# Motor_and_Encoder.net
KiCad netlist of a schematic drawn in Altium Designer
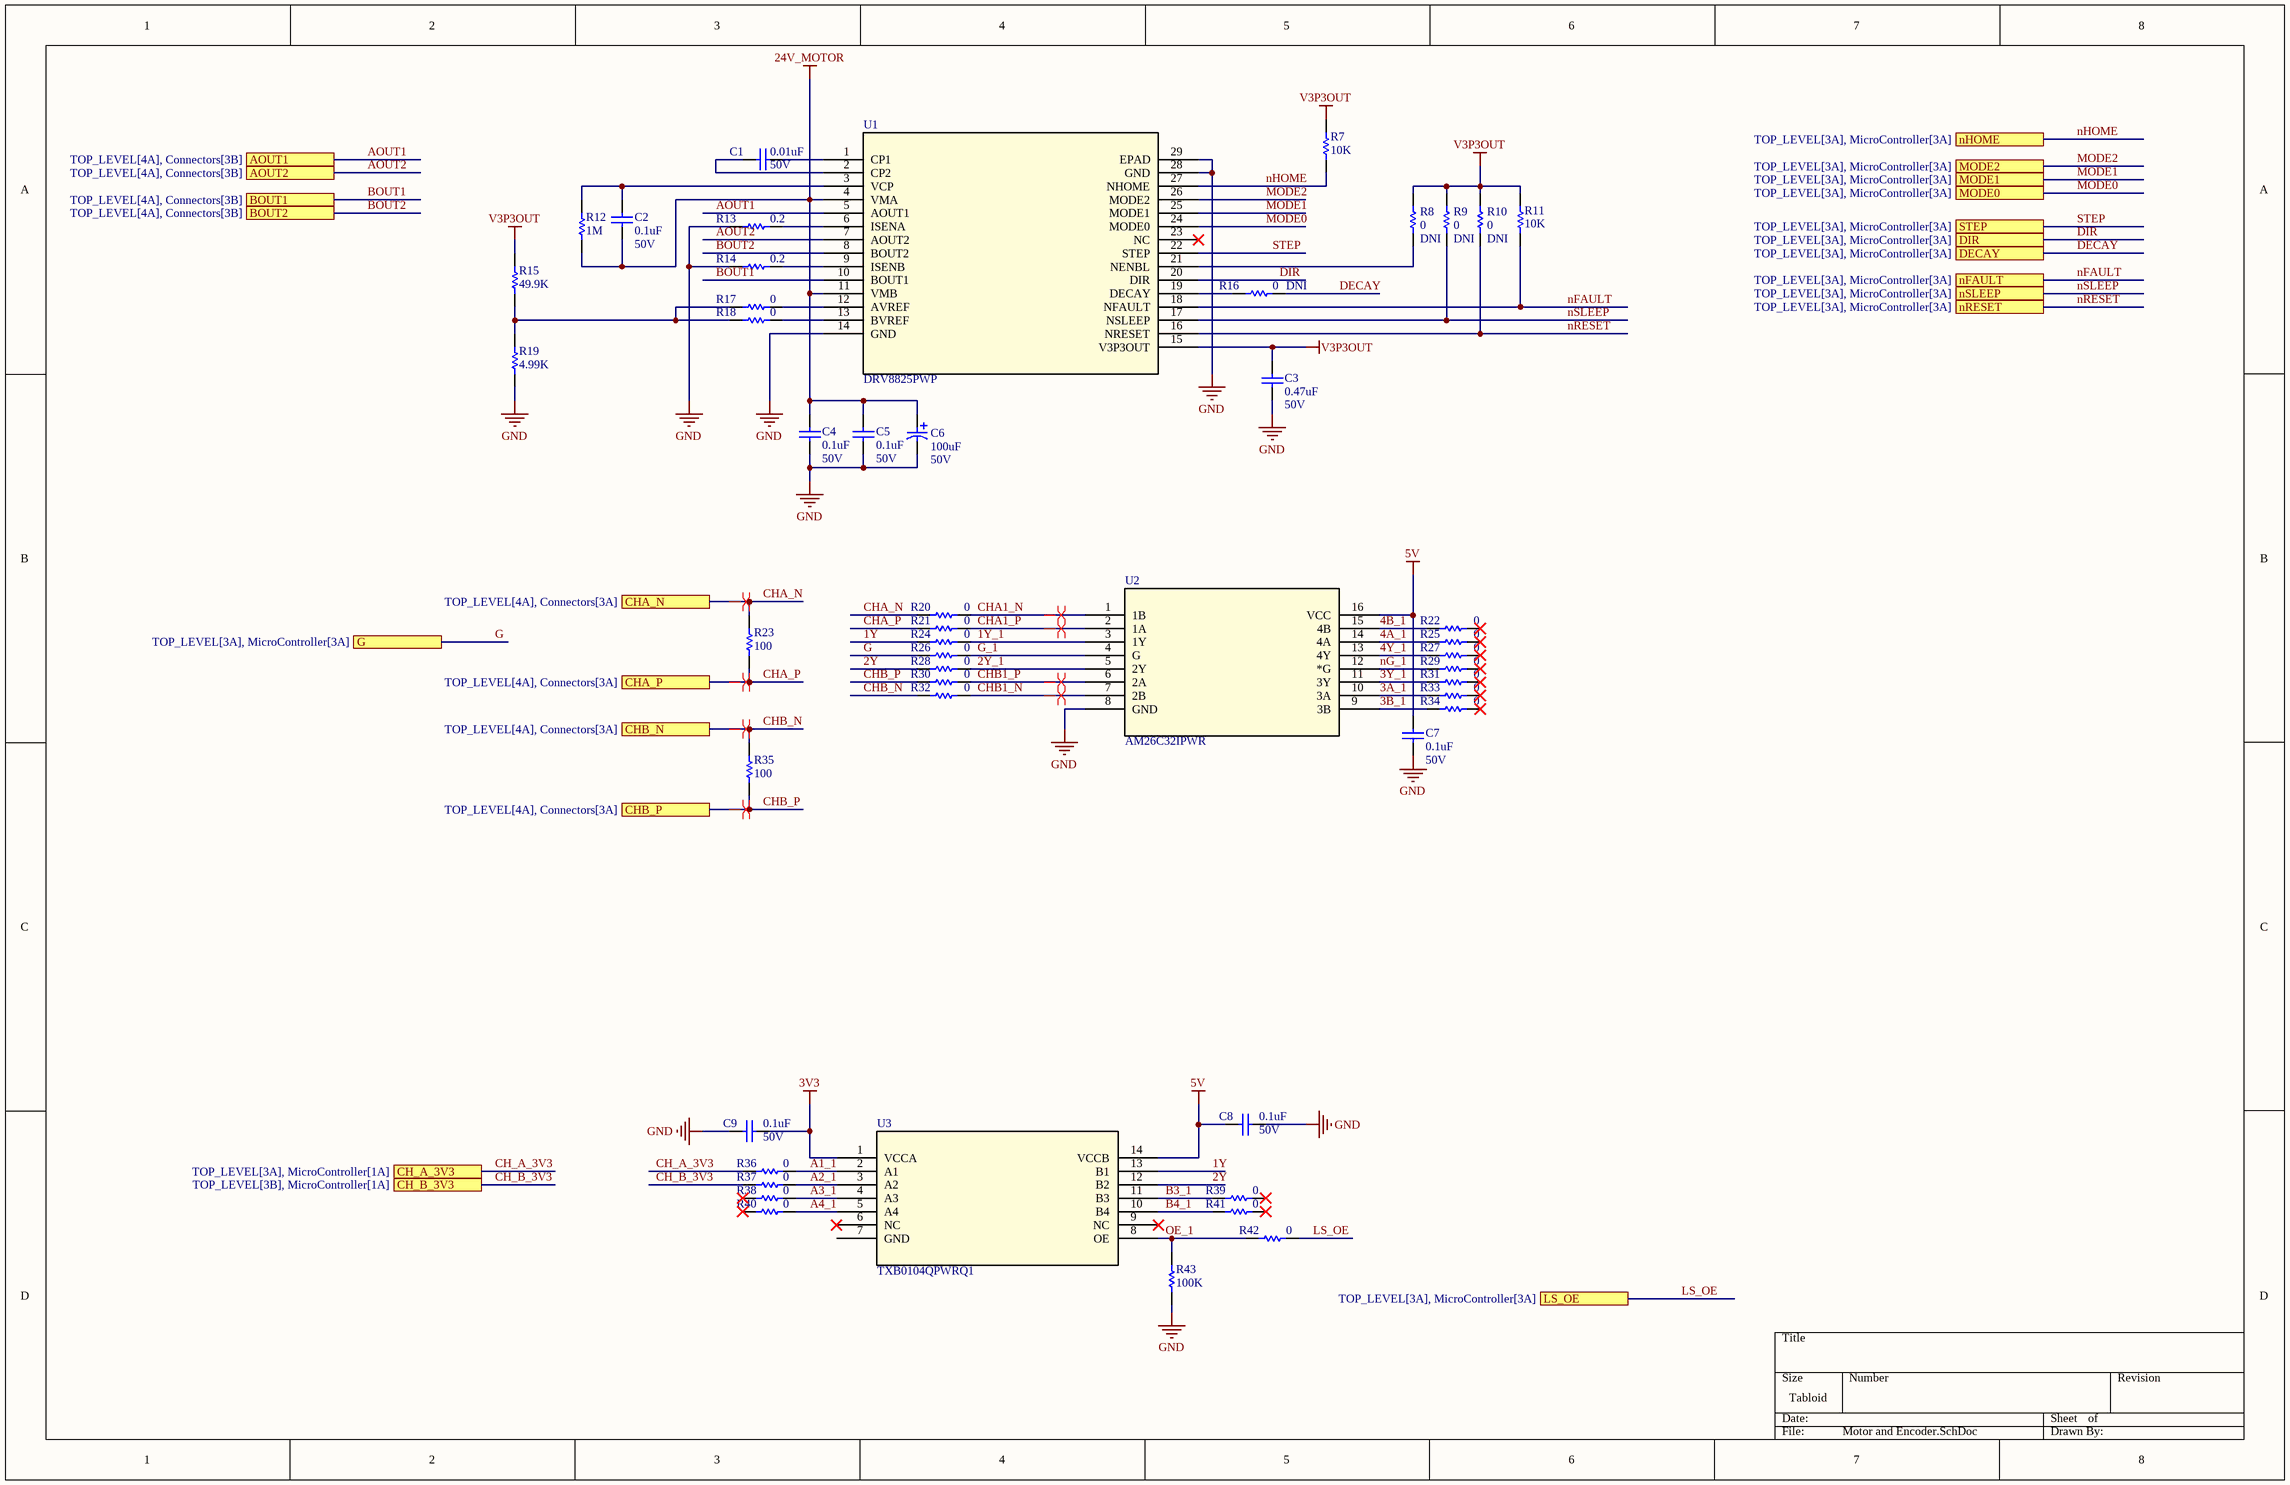
[diagram p0: Motor and Encoder.SchDoc]

(export (version "E")
  (design (tool "Eeschema 10.0.6"))
  (components
    (comp (ref "C1")
      (value "0.01uF")
      (footprint "DEFAULT_CAPACITOR_0805")
      (description "CAP CER 10000PF 50V X7R 0805")
      (fields
        (field (name "MANUFACTURER") "Cal-Chip Electronics, Inc.")
        (field (name "RATING") "50V")
        (field (name "Comment") "KGM21NR71H103KT")
      )
      (libsource (lib "Avery Altium Llibrary") (part "KGM21NR71H103KT"))
    )
    (comp (ref "C2")
      (value "0.1uF")
      (footprint "DEFAULT_CAPACITOR_0805")
      (description "CAP CER 0.1UF 50V X7R 0805")
      (fields
        (field (name "MANUFACTURER") "Cal-Chip Electronics, Inc.")
        (field (name "RATING") "50V")
        (field (name "Comment") "KGM21NR71H104KT")
      )
      (libsource (lib "Avery Altium Llibrary") (part "KGM21NR71H104KT"))
    )
    (comp (ref "C3")
      (value "0.47uF")
      (footprint "DEFAULT_CAPACITOR_0805")
      (description "CAP CER 0.47UF 50V X7R 0805")
      (fields
        (field (name "MANUFACTURER") "Cal-Chip Electronics, Inc.")
        (field (name "RATING") "50V")
        (field (name "Comment") "GRM21BR71H474KA88L")
      )
      (libsource (lib "Avery Altium Llibrary") (part "GRM21BR71H474KA88L"))
    )
    (comp (ref "C4")
      (value "0.1uF")
      (footprint "DEFAULT_CAPACITOR_0805")
      (description "CAP CER 0.1UF 50V X7R 0805")
      (fields
        (field (name "MANUFACTURER") "Cal-Chip Electronics, Inc.")
        (field (name "RATING") "50V")
        (field (name "Comment") "KGM21NR71H104KT")
      )
      (libsource (lib "Avery Altium Llibrary") (part "KGM21NR71H104KT"))
    )
    (comp (ref "C5")
      (value "0.1uF")
      (footprint "DEFAULT_CAPACITOR_0805")
      (description "CAP CER 0.1UF 50V X7R 0805")
      (fields
        (field (name "MANUFACTURER") "Cal-Chip Electronics, Inc.")
        (field (name "RATING") "50V")
        (field (name "Comment") "KGM21NR71H104KT")
      )
      (libsource (lib "Avery Altium Llibrary") (part "KGM21NR71H104KT"))
    )
    (comp (ref "C6")
      (value "100uF")
      (footprint "UWT1H101MNL1GS")
      (description "CAP ALUM 100UF 20% 50V SMD")
      (fields
        (field (name "MANUFACTURER_PART_NUMBER") "UWT1H101MNL1GS")
        (field (name "RATING") "50V")
        (field (name "COPYRIGHT") "Copyright (C) 2026 Ultra Librarian. All rights reserved.")
      )
      (libsource (lib "Avery Schem Library") (part "UWT1H101MNL1GS"))
    )
    (comp (ref "C7")
      (value "0.1uF")
      (footprint "DEFAULT_CAPACITOR_0805")
      (description "CAP CER 0.1UF 50V X7R 0805")
      (fields
        (field (name "MANUFACTURER") "Cal-Chip Electronics, Inc.")
        (field (name "RATING") "50V")
        (field (name "Comment") "KGM21NR71H104KT")
      )
      (libsource (lib "Avery Altium Llibrary") (part "KGM21NR71H104KT"))
    )
    (comp (ref "C8")
      (value "0.1uF")
      (footprint "DEFAULT_CAPACITOR_0805")
      (description "CAP CER 0.1UF 50V X7R 0805")
      (fields
        (field (name "MANUFACTURER") "Cal-Chip Electronics, Inc.")
        (field (name "RATING") "50V")
        (field (name "Comment") "KGM21NR71H104KT")
      )
      (libsource (lib "Avery Altium Llibrary") (part "KGM21NR71H104KT"))
    )
    (comp (ref "C9")
      (value "0.1uF")
      (footprint "DEFAULT_CAPACITOR_0805")
      (description "CAP CER 0.1UF 50V X7R 0805")
      (fields
        (field (name "MANUFACTURER") "Cal-Chip Electronics, Inc.")
        (field (name "RATING") "50V")
        (field (name "Comment") "KGM21NR71H104KT")
      )
      (libsource (lib "Avery Altium Llibrary") (part "KGM21NR71H104KT"))
    )
    (comp (ref "R7")
      (value "10K")
      (footprint "DEFAULT_RESISTOR_0805")
      (description "RES SMD 10K OHM 1% 1/4W 0805")
      (fields (field (name "POWER") "1/4W") (field (name "TOLERANCE") "1%"))
      (libsource (lib "Avery Altium Llibrary") (part "CRCW080510K0FKEA"))
    )
    (comp (ref "R8")
      (value "DNI")
      (footprint "DEFAULT_RESISTOR_0805")
      (description "RES 0 OHM JUMPER 1/8W 0805")
      (fields (field (name "POWER") "1/8W") (field (name "ALTIUM_VALUE") "0"))
      (libsource (lib "Avery Altium Llibrary") (part "RC0805JR-070RL"))
    )
    (comp (ref "R9")
      (value "DNI")
      (footprint "DEFAULT_RESISTOR_0805")
      (description "RES 0 OHM JUMPER 1/8W 0805")
      (fields (field (name "POWER") "1/8W") (field (name "ALTIUM_VALUE") "0"))
      (libsource (lib "Avery Altium Llibrary") (part "RC0805JR-070RL"))
    )
    (comp (ref "R10")
      (value "DNI")
      (footprint "DEFAULT_RESISTOR_0805")
      (description "RES 0 OHM JUMPER 1/8W 0805")
      (fields (field (name "POWER") "1/8W") (field (name "ALTIUM_VALUE") "0"))
      (libsource (lib "Avery Altium Llibrary") (part "RC0805JR-070RL"))
    )
    (comp (ref "R11")
      (value "10K")
      (footprint "DEFAULT_RESISTOR_0805")
      (description "RES SMD 10K OHM 1% 1/4W 0805")
      (fields (field (name "POWER") "1/4W") (field (name "TOLERANCE") "1%"))
      (libsource (lib "Avery Altium Llibrary") (part "CRCW080510K0FKEA"))
    )
    (comp (ref "R12")
      (value "1M")
      (footprint "DEFAULT_RESISTOR_0805")
      (description "RES SMD 1M OHM 1% 1/4W 0805")
      (fields (field (name "POWER") "1/4W") (field (name "TOLERANCE") "1%"))
      (libsource (lib "Avery Altium Llibrary") (part "CRCW08051M00FKEA"))
    )
    (comp (ref "R13")
      (value "0.2")
      (footprint "DEFAULT_RESISTOR_0805")
      (description "RES 0.2 OHM 1% 1/2W 0805")
      (fields (field (name "TOLERANCE") "1%") (field (name "Comment") "ERJ-6DSFR20V"))
      (libsource (lib "Avery Altium Llibrary") (part "ERJ-6DSFR20V"))
    )
    (comp (ref "R14")
      (value "0.2")
      (footprint "DEFAULT_RESISTOR_0805")
      (description "RES 0.2 OHM 1% 1/2W 0805")
      (fields (field (name "TOLERANCE") "1%") (field (name "Comment") "ERJ-6DSFR20V"))
      (libsource (lib "Avery Altium Llibrary") (part "ERJ-6DSFR20V"))
    )
    (comp (ref "R15")
      (value "49.9K")
      (footprint "DEFAULT_RESISTOR_0805")
      (description "RES 49.9K OHM 1% 1/8W 0805")
      (fields (field (name "POWER") "1/8W") (field (name "TOLERANCE") "1%"))
      (libsource (lib "Avery Altium Llibrary") (part "RMCF0805FT49K9"))
    )
    (comp (ref "R16")
      (value "DNI")
      (footprint "DEFAULT_RESISTOR_0805")
      (description "RES 0 OHM JUMPER 1/8W 0805")
      (fields (field (name "POWER") "1/8W") (field (name "ALTIUM_VALUE") "0"))
      (libsource (lib "Avery Altium Llibrary") (part "RC0805JR-070RL"))
    )
    (comp (ref "R17")
      (value "0")
      (footprint "DEFAULT_RESISTOR_0805")
      (description "RES 0 OHM JUMPER 1/8W 0805")
      (fields (field (name "POWER") "1/8W") (field (name "Comment") "RC0805JR-070RL"))
      (libsource (lib "Avery Altium Llibrary") (part "RC0805JR-070RL"))
    )
    (comp (ref "R18")
      (value "0")
      (footprint "DEFAULT_RESISTOR_0805")
      (description "RES 0 OHM JUMPER 1/8W 0805")
      (fields (field (name "POWER") "1/8W") (field (name "Comment") "RC0805JR-070RL"))
      (libsource (lib "Avery Altium Llibrary") (part "RC0805JR-070RL"))
    )
    (comp (ref "R19")
      (value "4.99K")
      (footprint "DEFAULT_RESISTOR_0805")
      (description "RES 4.99K OHM 1% 1/8W 0805")
      (fields (field (name "POWER") "1/8W") (field (name "TOLERANCE") "1%"))
      (libsource (lib "Avery Altium Llibrary") (part "RMCF0805FT4K99"))
    )
    (comp (ref "R20")
      (value "0")
      (footprint "DEFAULT_RESISTOR_0805")
      (description "RES 0 OHM JUMPER 1/8W 0805")
      (fields (field (name "POWER") "1/8W") (field (name "Comment") "RC0805JR-070RL"))
      (libsource (lib "Avery Altium Llibrary") (part "RC0805JR-070RL"))
    )
    (comp (ref "R21")
      (value "0")
      (footprint "DEFAULT_RESISTOR_0805")
      (description "RES 0 OHM JUMPER 1/8W 0805")
      (fields (field (name "POWER") "1/8W") (field (name "Comment") "RC0805JR-070RL"))
      (libsource (lib "Avery Altium Llibrary") (part "RC0805JR-070RL"))
    )
    (comp (ref "R22")
      (value "0")
      (footprint "DEFAULT_RESISTOR_0805")
      (description "RES 0 OHM JUMPER 1/8W 0805")
      (fields (field (name "POWER") "1/8W") (field (name "Comment") "RC0805JR-070RL"))
      (libsource (lib "Avery Altium Llibrary") (part "RC0805JR-070RL"))
    )
    (comp (ref "R23")
      (value "100")
      (footprint "DEFAULT_RESISTOR_0805")
      (description "RES SMD 100 OHM 1% 1/4W 0805")
      (fields (field (name "POWER") "1/4W") (field (name "TOLERANCE") "1%"))
      (libsource (lib "Avery Altium Llibrary") (part "CRCW0805100RFKEA"))
    )
    (comp (ref "R24")
      (value "0")
      (footprint "DEFAULT_RESISTOR_0805")
      (description "RES 0 OHM JUMPER 1/8W 0805")
      (fields (field (name "POWER") "1/8W") (field (name "Comment") "RC0805JR-070RL"))
      (libsource (lib "Avery Altium Llibrary") (part "RC0805JR-070RL"))
    )
    (comp (ref "R25")
      (value "0")
      (footprint "DEFAULT_RESISTOR_0805")
      (description "RES 0 OHM JUMPER 1/8W 0805")
      (fields (field (name "POWER") "1/8W") (field (name "Comment") "RC0805JR-070RL"))
      (libsource (lib "Avery Altium Llibrary") (part "RC0805JR-070RL"))
    )
    (comp (ref "R26")
      (value "0")
      (footprint "DEFAULT_RESISTOR_0805")
      (description "RES 0 OHM JUMPER 1/8W 0805")
      (fields (field (name "POWER") "1/8W") (field (name "Comment") "RC0805JR-070RL"))
      (libsource (lib "Avery Altium Llibrary") (part "RC0805JR-070RL"))
    )
    (comp (ref "R27")
      (value "0")
      (footprint "DEFAULT_RESISTOR_0805")
      (description "RES 0 OHM JUMPER 1/8W 0805")
      (fields (field (name "POWER") "1/8W") (field (name "Comment") "RC0805JR-070RL"))
      (libsource (lib "Avery Altium Llibrary") (part "RC0805JR-070RL"))
    )
    (comp (ref "R28")
      (value "0")
      (footprint "DEFAULT_RESISTOR_0805")
      (description "RES 0 OHM JUMPER 1/8W 0805")
      (fields (field (name "POWER") "1/8W") (field (name "Comment") "RC0805JR-070RL"))
      (libsource (lib "Avery Altium Llibrary") (part "RC0805JR-070RL"))
    )
    (comp (ref "R29")
      (value "0")
      (footprint "DEFAULT_RESISTOR_0805")
      (description "RES 0 OHM JUMPER 1/8W 0805")
      (fields (field (name "POWER") "1/8W") (field (name "Comment") "RC0805JR-070RL"))
      (libsource (lib "Avery Altium Llibrary") (part "RC0805JR-070RL"))
    )
    (comp (ref "R30")
      (value "0")
      (footprint "DEFAULT_RESISTOR_0805")
      (description "RES 0 OHM JUMPER 1/8W 0805")
      (fields (field (name "POWER") "1/8W") (field (name "Comment") "RC0805JR-070RL"))
      (libsource (lib "Avery Altium Llibrary") (part "RC0805JR-070RL"))
    )
    (comp (ref "R31")
      (value "0")
      (footprint "DEFAULT_RESISTOR_0805")
      (description "RES 0 OHM JUMPER 1/8W 0805")
      (fields (field (name "POWER") "1/8W") (field (name "Comment") "RC0805JR-070RL"))
      (libsource (lib "Avery Altium Llibrary") (part "RC0805JR-070RL"))
    )
    (comp (ref "R32")
      (value "0")
      (footprint "DEFAULT_RESISTOR_0805")
      (description "RES 0 OHM JUMPER 1/8W 0805")
      (fields (field (name "POWER") "1/8W") (field (name "Comment") "RC0805JR-070RL"))
      (libsource (lib "Avery Altium Llibrary") (part "RC0805JR-070RL"))
    )
    (comp (ref "R33")
      (value "0")
      (footprint "DEFAULT_RESISTOR_0805")
      (description "RES 0 OHM JUMPER 1/8W 0805")
      (fields (field (name "POWER") "1/8W") (field (name "Comment") "RC0805JR-070RL"))
      (libsource (lib "Avery Altium Llibrary") (part "RC0805JR-070RL"))
    )
    (comp (ref "R34")
      (value "0")
      (footprint "DEFAULT_RESISTOR_0805")
      (description "RES 0 OHM JUMPER 1/8W 0805")
      (fields (field (name "POWER") "1/8W") (field (name "Comment") "RC0805JR-070RL"))
      (libsource (lib "Avery Altium Llibrary") (part "RC0805JR-070RL"))
    )
    (comp (ref "R35")
      (value "100")
      (footprint "DEFAULT_RESISTOR_0805")
      (description "RES SMD 100 OHM 1% 1/4W 0805")
      (fields (field (name "POWER") "1/4W") (field (name "TOLERANCE") "1%"))
      (libsource (lib "Avery Altium Llibrary") (part "CRCW0805100RFKEA"))
    )
    (comp (ref "R36")
      (value "0")
      (footprint "DEFAULT_RESISTOR_0805")
      (description "RES 0 OHM JUMPER 1/8W 0805")
      (fields (field (name "POWER") "1/8W") (field (name "Comment") "RC0805JR-070RL"))
      (libsource (lib "Avery Altium Llibrary") (part "RC0805JR-070RL"))
    )
    (comp (ref "R37")
      (value "0")
      (footprint "DEFAULT_RESISTOR_0805")
      (description "RES 0 OHM JUMPER 1/8W 0805")
      (fields (field (name "POWER") "1/8W") (field (name "Comment") "RC0805JR-070RL"))
      (libsource (lib "Avery Altium Llibrary") (part "RC0805JR-070RL"))
    )
    (comp (ref "R38")
      (value "0")
      (footprint "DEFAULT_RESISTOR_0805")
      (description "RES 0 OHM JUMPER 1/8W 0805")
      (fields (field (name "POWER") "1/8W") (field (name "Comment") "RC0805JR-070RL"))
      (libsource (lib "Avery Altium Llibrary") (part "RC0805JR-070RL"))
    )
    (comp (ref "R39")
      (value "0")
      (footprint "DEFAULT_RESISTOR_0805")
      (description "RES 0 OHM JUMPER 1/8W 0805")
      (fields (field (name "POWER") "1/8W") (field (name "Comment") "RC0805JR-070RL"))
      (libsource (lib "Avery Altium Llibrary") (part "RC0805JR-070RL"))
    )
    (comp (ref "R40")
      (value "0")
      (footprint "DEFAULT_RESISTOR_0805")
      (description "RES 0 OHM JUMPER 1/8W 0805")
      (fields (field (name "POWER") "1/8W") (field (name "Comment") "RC0805JR-070RL"))
      (libsource (lib "Avery Altium Llibrary") (part "RC0805JR-070RL"))
    )
    (comp (ref "R41")
      (value "0")
      (footprint "DEFAULT_RESISTOR_0805")
      (description "RES 0 OHM JUMPER 1/8W 0805")
      (fields (field (name "POWER") "1/8W") (field (name "Comment") "RC0805JR-070RL"))
      (libsource (lib "Avery Altium Llibrary") (part "RC0805JR-070RL"))
    )
    (comp (ref "R42")
      (value "0")
      (footprint "DEFAULT_RESISTOR_0805")
      (description "RES 0 OHM JUMPER 1/8W 0805")
      (fields (field (name "POWER") "1/8W") (field (name "Comment") "RC0805JR-070RL"))
      (libsource (lib "Avery Altium Llibrary") (part "RC0805JR-070RL"))
    )
    (comp (ref "R43")
      (value "100K")
      (footprint "DEFAULT_RESISTOR_0805")
      (description "RES 100K OHM 1% 1/8W 0805")
      (fields (field (name "POWER") "1/8W") (field (name "TOLERANCE") "1%"))
      (libsource (lib "Avery Altium Llibrary") (part "RC0805FR-07100KL"))
    )
    (comp (ref "U1")
      (value "DRV8825PWP")
      (footprint "DRV8825PWP - 28HTSSTOP")
      (fields (field (name "COPYRIGHT") "Copyright (C) 2026 Ultra Librarian. All rights reserved."))
      (libsource (lib "Avery Schem Library") (part "DRV8825PWP"))
    )
    (comp (ref "U2")
      (value "AM26C32IPWR")
      (footprint "AM26C32IPWR")
      (description "Quadruple Differential Line Receiver 16-TSSOP -40 to 85")
      (fields (field (name "COPYRIGHT") "Copyright (C) 2025 Ultra Librarian. All rights reserved."))
      (libsource (lib "Avery Schem Library") (part "AM26C32IPWR"))
    )
    (comp (ref "U3")
      (value "TXB0104QPWRQ1")
      (footprint "TXB0104QPWRQ1 - 14TSSOP")
      (fields (field (name "COPYRIGHT") "Copyright (C) 2025 Ultra Librarian. All rights reserved."))
      (libsource (lib "Avery Schem Library") (part "TXB0104QPWRQ1"))
    )
  )
  (nets
    (net (code "1") (name "/1Y") (class "Default")
      (node (ref "R24") (pin "2") (pinfunction "2_2") (pintype "passive"))
      (node (ref "U3") (pin "13") (pinfunction "B1_13") (pintype "passive"))
    )
    (net (code "2") (name "/1Y_1") (class "Default")
      (node (ref "R24") (pin "1") (pinfunction "1_1") (pintype "passive"))
      (node (ref "U2") (pin "3") (pinfunction "1Y_3") (pintype "passive"))
    )
    (net (code "3") (name "/2Y") (class "Default")
      (node (ref "R28") (pin "2") (pinfunction "2_2") (pintype "passive"))
      (node (ref "U3") (pin "12") (pinfunction "B2_12") (pintype "passive"))
    )
    (net (code "4") (name "/2Y_1") (class "Default")
      (node (ref "R28") (pin "1") (pinfunction "1_1") (pintype "passive"))
      (node (ref "U2") (pin "5") (pinfunction "2Y_5") (pintype "passive"))
    )
    (net (code "5") (name "/3A_1") (class "Default")
      (node (ref "R33") (pin "2") (pinfunction "2_2") (pintype "passive"))
      (node (ref "U2") (pin "10") (pinfunction "3A_10") (pintype "passive"))
    )
    (net (code "6") (name "/3B_1") (class "Default")
      (node (ref "R34") (pin "2") (pinfunction "2_2") (pintype "passive"))
      (node (ref "U2") (pin "9") (pinfunction "3B_9") (pintype "passive"))
    )
    (net (code "7") (name "/3Y_1") (class "Default")
      (node (ref "R31") (pin "2") (pinfunction "2_2") (pintype "passive"))
      (node (ref "U2") (pin "11") (pinfunction "3Y_11") (pintype "passive"))
    )
    (net (code "8") (name "/4A_1") (class "Default")
      (node (ref "R25") (pin "2") (pinfunction "2_2") (pintype "passive"))
      (node (ref "U2") (pin "14") (pinfunction "4A_14") (pintype "passive"))
    )
    (net (code "9") (name "/4B_1") (class "Default")
      (node (ref "R22") (pin "2") (pinfunction "2_2") (pintype "passive"))
      (node (ref "U2") (pin "15") (pinfunction "4B_15") (pintype "passive"))
    )
    (net (code "10") (name "/4Y_1") (class "Default")
      (node (ref "R27") (pin "2") (pinfunction "2_2") (pintype "passive"))
      (node (ref "U2") (pin "13") (pinfunction "4Y_13") (pintype "passive"))
    )
    (net (code "11") (name "/A1_1") (class "Default")
      (node (ref "R36") (pin "1") (pinfunction "1_1") (pintype "passive"))
      (node (ref "U3") (pin "2") (pinfunction "A1_2") (pintype "passive"))
    )
    (net (code "12") (name "/A2_1") (class "Default")
      (node (ref "R37") (pin "1") (pinfunction "1_1") (pintype "passive"))
      (node (ref "U3") (pin "3") (pinfunction "A2_3") (pintype "passive"))
    )
    (net (code "13") (name "/A3_1") (class "Default")
      (node (ref "R38") (pin "1") (pinfunction "1_1") (pintype "passive"))
      (node (ref "U3") (pin "4") (pinfunction "A3_4") (pintype "passive"))
    )
    (net (code "14") (name "/A4_1") (class "Default")
      (node (ref "R40") (pin "1") (pinfunction "1_1") (pintype "passive"))
      (node (ref "U3") (pin "5") (pinfunction "A4_5") (pintype "passive"))
    )
    (net (code "15") (name "/AOUT1") (class "Default")
      (node (ref "U1") (pin "5") (pinfunction "AOUT1_5") (pintype "passive"))
    )
    (net (code "16") (name "/AOUT2") (class "Default")
      (node (ref "U1") (pin "7") (pinfunction "AOUT2_7") (pintype "passive"))
    )
    (net (code "17") (name "/B3_1") (class "Default")
      (node (ref "R39") (pin "2") (pinfunction "2_2") (pintype "passive"))
      (node (ref "U3") (pin "11") (pinfunction "B3_11") (pintype "passive"))
    )
    (net (code "18") (name "/B4_1") (class "Default")
      (node (ref "R41") (pin "2") (pinfunction "2_2") (pintype "passive"))
      (node (ref "U3") (pin "10") (pinfunction "B4_10") (pintype "passive"))
    )
    (net (code "19") (name "/BOUT1") (class "Default")
      (node (ref "U1") (pin "10") (pinfunction "BOUT1_10") (pintype "passive"))
    )
    (net (code "20") (name "/BOUT2") (class "Default")
      (node (ref "U1") (pin "8") (pinfunction "BOUT2_8") (pintype "passive"))
    )
    (net (code "21") (name "/CHA1_N") (class "Default")
      (node (ref "R20") (pin "1") (pinfunction "1_1") (pintype "passive"))
      (node (ref "U2") (pin "1") (pinfunction "1B_1") (pintype "passive"))
    )
    (net (code "22") (name "/CHA1_P") (class "Default")
      (node (ref "R21") (pin "1") (pinfunction "1_1") (pintype "passive"))
      (node (ref "U2") (pin "2") (pinfunction "1A_2") (pintype "passive"))
    )
    (net (code "23") (name "/CHA_N") (class "Default")
      (node (ref "R20") (pin "2") (pinfunction "2_2") (pintype "passive"))
      (node (ref "R23") (pin "1") (pinfunction "1_1") (pintype "passive"))
    )
    (net (code "24") (name "/CHA_P") (class "Default")
      (node (ref "R21") (pin "2") (pinfunction "2_2") (pintype "passive"))
      (node (ref "R23") (pin "2") (pinfunction "2_2") (pintype "passive"))
    )
    (net (code "25") (name "/CHB1_N") (class "Default")
      (node (ref "R32") (pin "1") (pinfunction "1_1") (pintype "passive"))
      (node (ref "U2") (pin "7") (pinfunction "2B_7") (pintype "passive"))
    )
    (net (code "26") (name "/CHB1_P") (class "Default")
      (node (ref "R30") (pin "1") (pinfunction "1_1") (pintype "passive"))
      (node (ref "U2") (pin "6") (pinfunction "2A_6") (pintype "passive"))
    )
    (net (code "27") (name "/CHB_N") (class "Default")
      (node (ref "R32") (pin "2") (pinfunction "2_2") (pintype "passive"))
      (node (ref "R35") (pin "1") (pinfunction "1_1") (pintype "passive"))
    )
    (net (code "28") (name "/CHB_P") (class "Default")
      (node (ref "R30") (pin "2") (pinfunction "2_2") (pintype "passive"))
      (node (ref "R35") (pin "2") (pinfunction "2_2") (pintype "passive"))
    )
    (net (code "29") (name "/CH_A_3V3") (class "Default")
      (node (ref "R36") (pin "2") (pinfunction "2_2") (pintype "passive"))
    )
    (net (code "30") (name "/CH_B_3V3") (class "Default")
      (node (ref "R37") (pin "2") (pinfunction "2_2") (pintype "passive"))
    )
    (net (code "31") (name "/DECAY") (class "Default")
      (node (ref "R16") (pin "1") (pinfunction "1_1") (pintype "passive"))
    )
    (net (code "32") (name "/DIR") (class "Default")
      (node (ref "U1") (pin "20") (pinfunction "DIR_20") (pintype "passive"))
    )
    (net (code "33") (name "/G") (class "Default")
      (node (ref "R26") (pin "2") (pinfunction "2_2") (pintype "passive"))
    )
    (net (code "34") (name "/G_1") (class "Default")
      (node (ref "R26") (pin "1") (pinfunction "1_1") (pintype "passive"))
      (node (ref "U2") (pin "4") (pinfunction "G_4") (pintype "passive"))
    )
    (net (code "35") (name "/LS_OE") (class "Default")
      (node (ref "R42") (pin "1") (pinfunction "1_1") (pintype "passive"))
    )
    (net (code "36") (name "/MODE0") (class "Default")
      (node (ref "U1") (pin "24") (pinfunction "MODE0_24") (pintype "passive"))
    )
    (net (code "37") (name "/MODE1") (class "Default")
      (node (ref "U1") (pin "25") (pinfunction "MODE1_25") (pintype "passive"))
    )
    (net (code "38") (name "/MODE2") (class "Default")
      (node (ref "U1") (pin "26") (pinfunction "MODE2_26") (pintype "passive"))
    )
    (net (code "39") (name "/OE_1") (class "Default")
      (node (ref "R42") (pin "2") (pinfunction "2_2") (pintype "passive"))
      (node (ref "R43") (pin "1") (pinfunction "1_1") (pintype "passive"))
      (node (ref "U3") (pin "8") (pinfunction "OE_8") (pintype "passive"))
    )
    (net (code "40") (name "/STEP") (class "Default")
      (node (ref "U1") (pin "22") (pinfunction "STEP_22") (pintype "passive"))
    )
    (net (code "41") (name "/nFAULT") (class "Default")
      (node (ref "R11") (pin "2") (pinfunction "2_2") (pintype "passive"))
      (node (ref "U1") (pin "18") (pinfunction "NFAULT_18") (pintype "passive"))
    )
    (net (code "42") (name "/nG_1") (class "Default")
      (node (ref "R29") (pin "2") (pinfunction "2_2") (pintype "passive"))
      (node (ref "U2") (pin "12") (pinfunction "*G_12") (pintype "passive"))
    )
    (net (code "43") (name "/nHOME") (class "Default")
      (node (ref "R7") (pin "2") (pinfunction "2_2") (pintype "passive"))
      (node (ref "U1") (pin "27") (pinfunction "NHOME_27") (pintype "passive"))
    )
    (net (code "44") (name "/nRESET") (class "Default")
      (node (ref "R10") (pin "2") (pinfunction "2_2") (pintype "passive"))
      (node (ref "U1") (pin "16") (pinfunction "NRESET_16") (pintype "passive"))
    )
    (net (code "45") (name "/nSLEEP") (class "Default")
      (node (ref "R9") (pin "2") (pinfunction "2_2") (pintype "passive"))
      (node (ref "U1") (pin "17") (pinfunction "NSLEEP_17") (pintype "passive"))
    )
    (net (code "46") (name "3V3") (class "Default")
      (node (ref "C9") (pin "1") (pinfunction "1_1") (pintype "passive"))
      (node (ref "U3") (pin "1") (pinfunction "VCCA_1") (pintype "power_in"))
    )
    (net (code "47") (name "5V") (class "Default")
      (node (ref "C7") (pin "2") (pinfunction "2_2") (pintype "passive"))
      (node (ref "C8") (pin "2") (pinfunction "2_2") (pintype "passive"))
      (node (ref "U2") (pin "16") (pinfunction "VCC_16") (pintype "power_in"))
      (node (ref "U3") (pin "14") (pinfunction "VCCB_14") (pintype "power_in"))
    )
    (net (code "48") (name "24V_MOTOR") (class "Default")
      (node (ref "C2") (pin "2") (pinfunction "2_2") (pintype "passive"))
      (node (ref "C4") (pin "1") (pinfunction "1_1") (pintype "passive"))
      (node (ref "C5") (pin "1") (pinfunction "1_1") (pintype "passive"))
      (node (ref "C6") (pin "1") (pinfunction "1_1") (pintype "passive"))
      (node (ref "R12") (pin "2") (pinfunction "2_2") (pintype "passive"))
      (node (ref "U1") (pin "11") (pinfunction "VMB_11") (pintype "power_in"))
      (node (ref "U1") (pin "4") (pinfunction "VMA_4") (pintype "power_in"))
    )
    (net (code "49") (name "GND") (class "Default")
      (node (ref "C3") (pin "1") (pinfunction "1_1") (pintype "passive"))
      (node (ref "C4") (pin "2") (pinfunction "2_2") (pintype "passive"))
      (node (ref "C5") (pin "2") (pinfunction "2_2") (pintype "passive"))
      (node (ref "C6") (pin "2") (pinfunction "2_2") (pintype "passive"))
      (node (ref "C7") (pin "1") (pinfunction "1_1") (pintype "passive"))
      (node (ref "C8") (pin "1") (pinfunction "1_1") (pintype "passive"))
      (node (ref "C9") (pin "2") (pinfunction "2_2") (pintype "passive"))
      (node (ref "R13") (pin "2") (pinfunction "2_2") (pintype "passive"))
      (node (ref "R14") (pin "2") (pinfunction "2_2") (pintype "passive"))
      (node (ref "R19") (pin "2") (pinfunction "2_2") (pintype "passive"))
      (node (ref "R43") (pin "2") (pinfunction "2_2") (pintype "passive"))
      (node (ref "U1") (pin "14") (pinfunction "GND_14") (pintype "power_in"))
      (node (ref "U1") (pin "28") (pinfunction "GND_28") (pintype "power_in"))
      (node (ref "U1") (pin "29") (pinfunction "EPAD_29") (pintype "passive"))
      (node (ref "U2") (pin "8") (pinfunction "GND_8") (pintype "power_in"))
    )
    (net (code "50") (name "Net-(R15-Pad2)") (class "Default")
      (node (ref "R15") (pin "2") (pinfunction "2_2") (pintype "passive"))
      (node (ref "R17") (pin "2") (pinfunction "2_2") (pintype "passive"))
      (node (ref "R18") (pin "2") (pinfunction "2_2") (pintype "passive"))
      (node (ref "R19") (pin "1") (pinfunction "1_1") (pintype "passive"))
    )
    (net (code "51") (name "Net-(U1-AVREF)") (class "Default")
      (node (ref "R17") (pin "1") (pinfunction "1_1") (pintype "passive"))
      (node (ref "U1") (pin "12") (pinfunction "AVREF_12") (pintype "passive"))
    )
    (net (code "52") (name "Net-(U1-BVREF)") (class "Default")
      (node (ref "R18") (pin "1") (pinfunction "1_1") (pintype "passive"))
      (node (ref "U1") (pin "13") (pinfunction "BVREF_13") (pintype "passive"))
    )
    (net (code "53") (name "Net-(U1-CP1)") (class "Default")
      (node (ref "C1") (pin "1") (pinfunction "1_1") (pintype "passive"))
      (node (ref "U1") (pin "1") (pinfunction "CP1_1") (pintype "passive"))
    )
    (net (code "54") (name "Net-(U1-CP2)") (class "Default")
      (node (ref "C1") (pin "2") (pinfunction "2_2") (pintype "passive"))
      (node (ref "U1") (pin "2") (pinfunction "CP2_2") (pintype "passive"))
    )
    (net (code "55") (name "Net-(U1-DECAY)") (class "Default")
      (node (ref "R16") (pin "2") (pinfunction "2_2") (pintype "passive"))
      (node (ref "U1") (pin "19") (pinfunction "DECAY_19") (pintype "passive"))
    )
    (net (code "56") (name "Net-(U1-ISENA)") (class "Default")
      (node (ref "R13") (pin "1") (pinfunction "1_1") (pintype "passive"))
      (node (ref "U1") (pin "6") (pinfunction "ISENA_6") (pintype "passive"))
    )
    (net (code "57") (name "Net-(U1-ISENB)") (class "Default")
      (node (ref "R14") (pin "1") (pinfunction "1_1") (pintype "passive"))
      (node (ref "U1") (pin "9") (pinfunction "ISENB_9") (pintype "passive"))
    )
    (net (code "58") (name "Net-(U1-NENBL)") (class "Default")
      (node (ref "R8") (pin "2") (pinfunction "2_2") (pintype "passive"))
      (node (ref "U1") (pin "21") (pinfunction "NENBL_21") (pintype "passive"))
    )
    (net (code "59") (name "Net-(U1-VCP)") (class "Default")
      (node (ref "C2") (pin "1") (pinfunction "1_1") (pintype "passive"))
      (node (ref "R12") (pin "1") (pinfunction "1_1") (pintype "passive"))
      (node (ref "U1") (pin "3") (pinfunction "VCP_3") (pintype "passive"))
    )
    (net (code "60") (name "V3P3OUT") (class "Default")
      (node (ref "C3") (pin "2") (pinfunction "2_2") (pintype "passive"))
      (node (ref "R10") (pin "1") (pinfunction "1_1") (pintype "passive"))
      (node (ref "R11") (pin "1") (pinfunction "1_1") (pintype "passive"))
      (node (ref "R15") (pin "1") (pinfunction "1_1") (pintype "passive"))
      (node (ref "R7") (pin "1") (pinfunction "1_1") (pintype "passive"))
      (node (ref "R8") (pin "1") (pinfunction "1_1") (pintype "passive"))
      (node (ref "R9") (pin "1") (pinfunction "1_1") (pintype "passive"))
      (node (ref "U1") (pin "15") (pinfunction "V3P3OUT_15") (pintype "passive"))
    )
    (net (code "61") (name "unconnected-(R22-Pad1)") (class "Default")
      (node (ref "R22") (pin "1") (pinfunction "1_1") (pintype "passive+no_connect"))
    )
    (net (code "62") (name "unconnected-(R25-Pad1)") (class "Default")
      (node (ref "R25") (pin "1") (pinfunction "1_1") (pintype "passive+no_connect"))
    )
    (net (code "63") (name "unconnected-(R27-Pad1)") (class "Default")
      (node (ref "R27") (pin "1") (pinfunction "1_1") (pintype "passive+no_connect"))
    )
    (net (code "64") (name "unconnected-(R29-Pad1)") (class "Default")
      (node (ref "R29") (pin "1") (pinfunction "1_1") (pintype "passive+no_connect"))
    )
    (net (code "65") (name "unconnected-(R31-Pad1)") (class "Default")
      (node (ref "R31") (pin "1") (pinfunction "1_1") (pintype "passive+no_connect"))
    )
    (net (code "66") (name "unconnected-(R33-Pad1)") (class "Default")
      (node (ref "R33") (pin "1") (pinfunction "1_1") (pintype "passive+no_connect"))
    )
    (net (code "67") (name "unconnected-(R34-Pad1)") (class "Default")
      (node (ref "R34") (pin "1") (pinfunction "1_1") (pintype "passive+no_connect"))
    )
    (net (code "68") (name "unconnected-(R38-Pad2)") (class "Default")
      (node (ref "R38") (pin "2") (pinfunction "2_2") (pintype "passive+no_connect"))
    )
    (net (code "69") (name "unconnected-(R39-Pad1)") (class "Default")
      (node (ref "R39") (pin "1") (pinfunction "1_1") (pintype "passive+no_connect"))
    )
    (net (code "70") (name "unconnected-(R40-Pad2)") (class "Default")
      (node (ref "R40") (pin "2") (pinfunction "2_2") (pintype "passive+no_connect"))
    )
    (net (code "71") (name "unconnected-(R41-Pad1)") (class "Default")
      (node (ref "R41") (pin "1") (pinfunction "1_1") (pintype "passive+no_connect"))
    )
    (net (code "72") (name "unconnected-(U1-NC-Pad23)") (class "Default")
      (node (ref "U1") (pin "23") (pinfunction "NC_23") (pintype "passive+no_connect"))
    )
    (net (code "73") (name "unconnected-(U3-GND-Pad7)") (class "Default")
      (node (ref "U3") (pin "7") (pinfunction "GND_7") (pintype "power_in"))
    )
    (net (code "74") (name "unconnected-(U3-NC-Pad6)") (class "Default")
      (node (ref "U3") (pin "6") (pinfunction "NC_6") (pintype "passive+no_connect"))
    )
    (net (code "75") (name "unconnected-(U3-NC-Pad9)") (class "Default")
      (node (ref "U3") (pin "9") (pinfunction "NC_9") (pintype "passive+no_connect"))
    )
  )
)
